# ESP32_S3_Wroom2_Schematic.net
KiCad netlist of a schematic drawn in Altium Designer
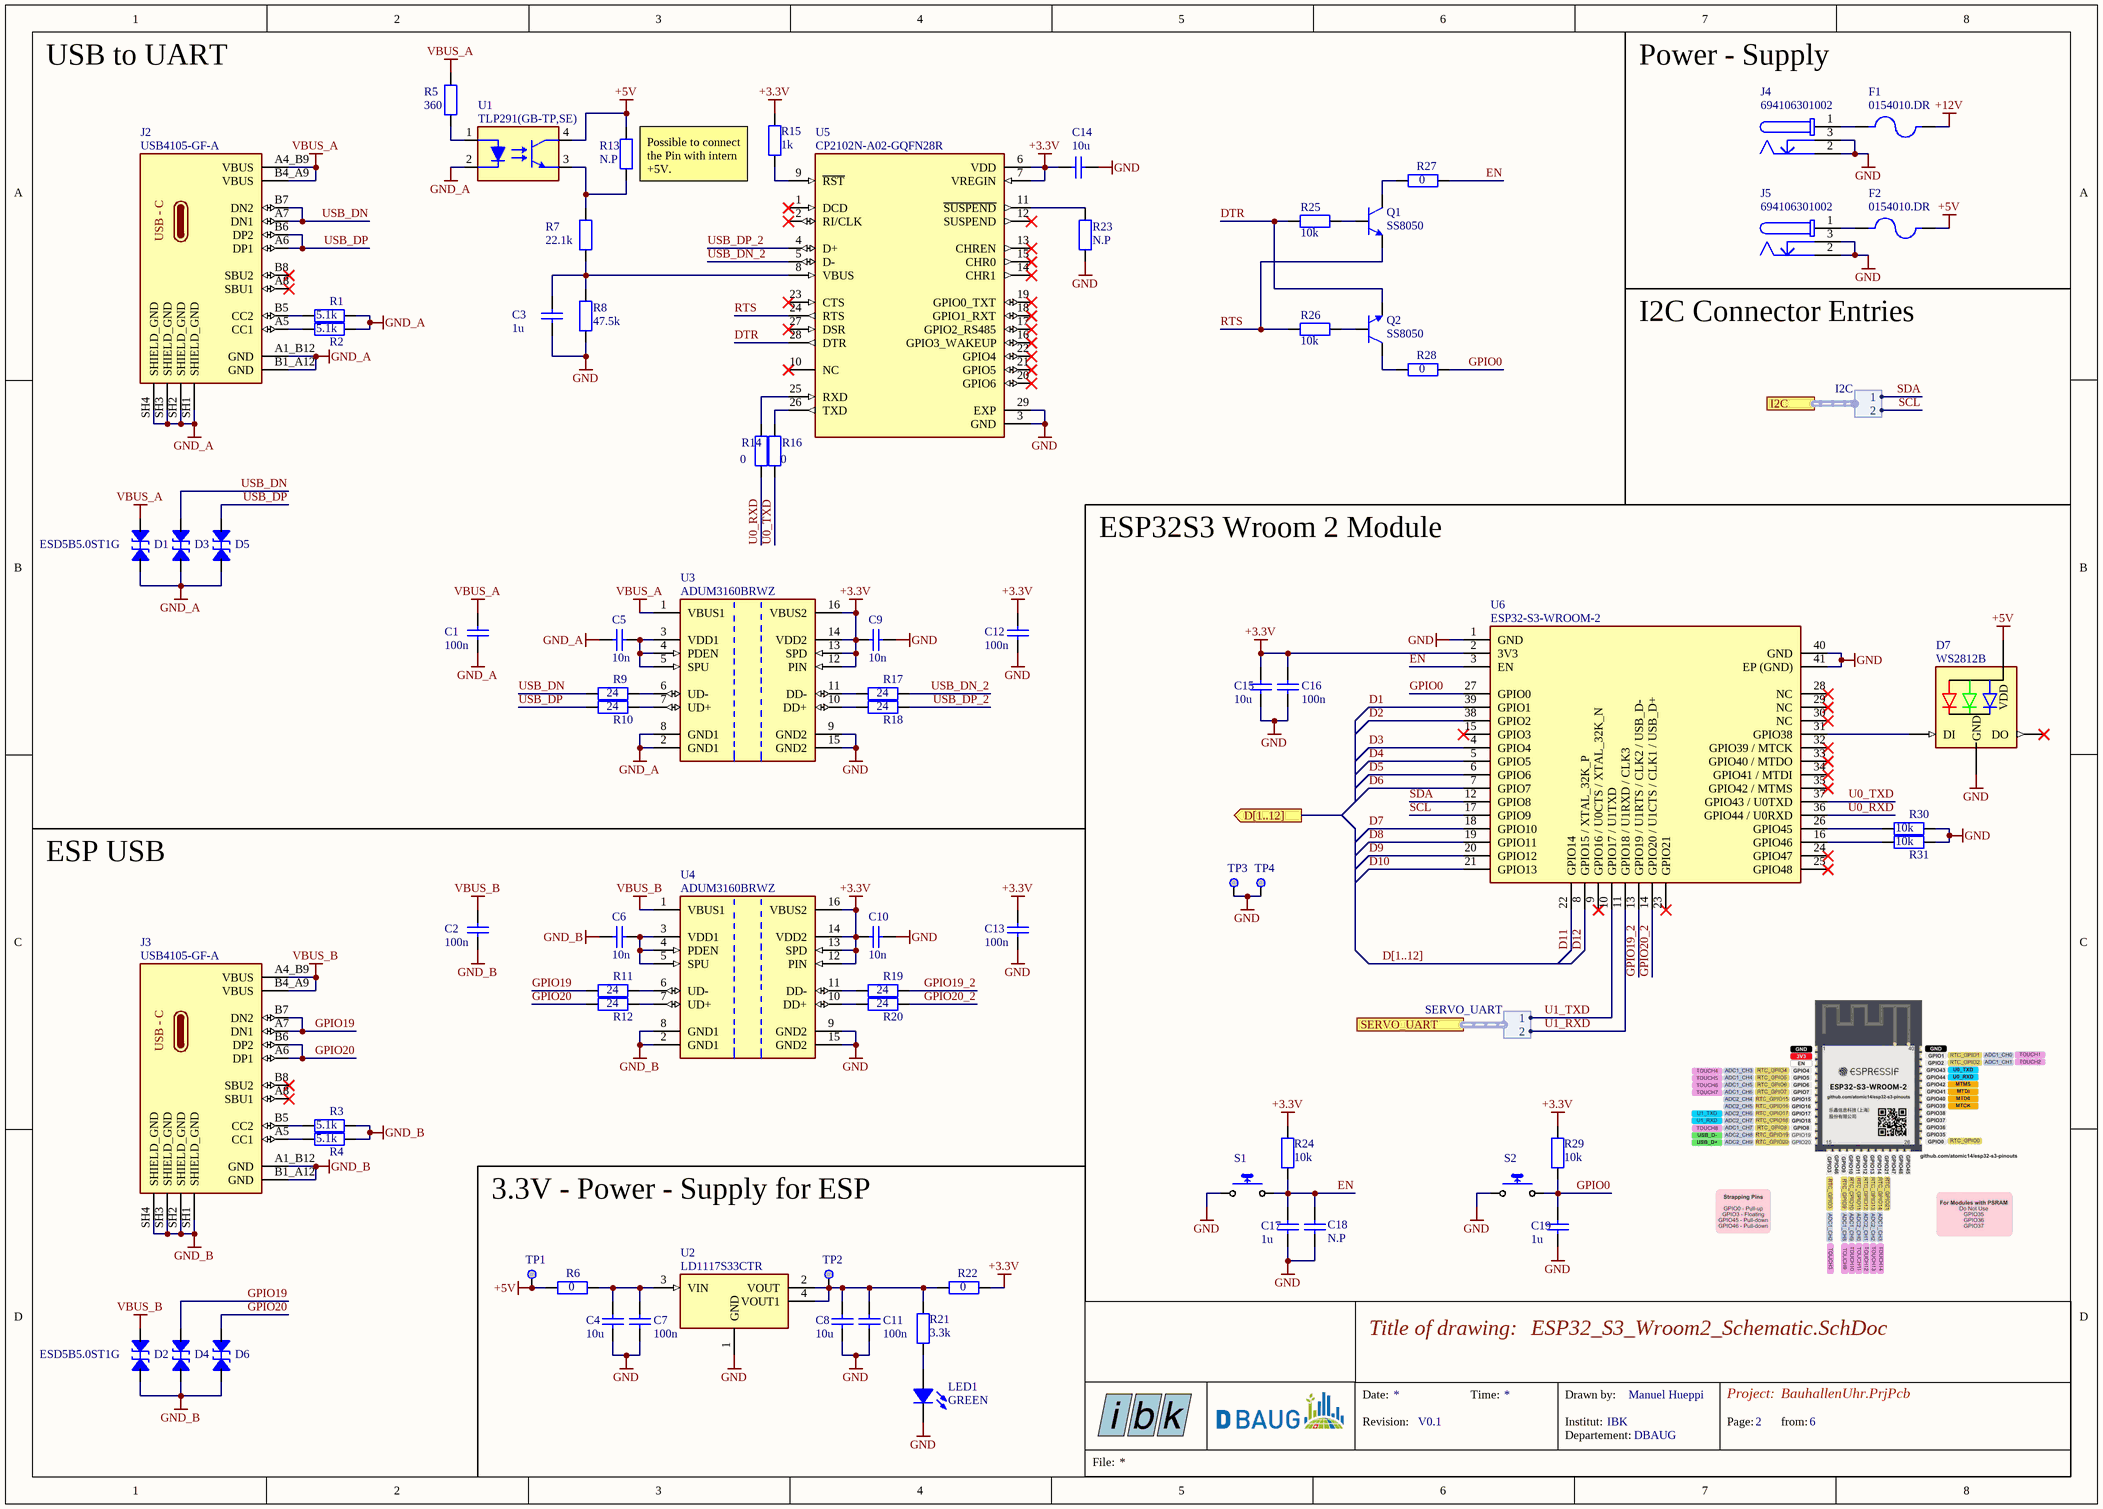
[diagram p0: ESP32_S3_Wroom2_Schematic.SchDoc]

(export (version "E")
  (design (tool "Eeschema 10.0.6"))
  (components
    (comp (ref "C1")
      (value "100n")
      (footprint "PCB_Altium_Library_Manuel:0603_CAPACITOR")
      (description "0603")
      (libsource (lib "Schematic_Altium_Library_Manuel") (part "Capacitor"))
    )
    (comp (ref "C2")
      (value "100n")
      (footprint "PCB_Altium_Library_Manuel:0603_CAPACITOR")
      (description "0603")
      (libsource (lib "Schematic_Altium_Library_Manuel") (part "Capacitor"))
    )
    (comp (ref "C3")
      (value "1u")
      (footprint "PCB_Altium_Library_Manuel:0603_CAPACITOR")
      (description "0603")
      (libsource (lib "Schematic_Altium_Library_Manuel") (part "Capacitor"))
    )
    (comp (ref "C4")
      (value "10u")
      (footprint "PCB_Altium_Library_Manuel:0603_CAPACITOR")
      (description "0603")
      (libsource (lib "Schematic_Altium_Library_Manuel") (part "Capacitor"))
    )
    (comp (ref "C5")
      (value "10n")
      (footprint "PCB_Altium_Library_Manuel:0603_CAPACITOR")
      (description "0603")
      (libsource (lib "Schematic_Altium_Library_Manuel") (part "Capacitor"))
    )
    (comp (ref "C6")
      (value "10n")
      (footprint "PCB_Altium_Library_Manuel:0603_CAPACITOR")
      (description "0603")
      (libsource (lib "Schematic_Altium_Library_Manuel") (part "Capacitor"))
    )
    (comp (ref "C7")
      (value "100n")
      (footprint "PCB_Altium_Library_Manuel:0603_CAPACITOR")
      (description "0603")
      (libsource (lib "Schematic_Altium_Library_Manuel") (part "Capacitor"))
    )
    (comp (ref "C8")
      (value "10u")
      (footprint "PCB_Altium_Library_Manuel:0603_CAPACITOR")
      (description "0603")
      (libsource (lib "Schematic_Altium_Library_Manuel") (part "Capacitor"))
    )
    (comp (ref "C9")
      (value "10n")
      (footprint "PCB_Altium_Library_Manuel:0603_CAPACITOR")
      (description "0603")
      (libsource (lib "Schematic_Altium_Library_Manuel") (part "Capacitor"))
    )
    (comp (ref "C10")
      (value "10n")
      (footprint "PCB_Altium_Library_Manuel:0603_CAPACITOR")
      (description "0603")
      (libsource (lib "Schematic_Altium_Library_Manuel") (part "Capacitor"))
    )
    (comp (ref "C11")
      (value "100n")
      (footprint "PCB_Altium_Library_Manuel:0603_CAPACITOR")
      (description "0603")
      (libsource (lib "Schematic_Altium_Library_Manuel") (part "Capacitor"))
    )
    (comp (ref "C12")
      (value "100n")
      (footprint "PCB_Altium_Library_Manuel:0603_CAPACITOR")
      (description "0603")
      (libsource (lib "Schematic_Altium_Library_Manuel") (part "Capacitor"))
    )
    (comp (ref "C13")
      (value "100n")
      (footprint "PCB_Altium_Library_Manuel:0603_CAPACITOR")
      (description "0603")
      (libsource (lib "Schematic_Altium_Library_Manuel") (part "Capacitor"))
    )
    (comp (ref "C14")
      (value "10u")
      (footprint "PCB_Altium_Library_Manuel:0603_CAPACITOR")
      (description "0603")
      (libsource (lib "Schematic_Altium_Library_Manuel") (part "Capacitor"))
    )
    (comp (ref "C15")
      (value "10u")
      (footprint "PCB_Altium_Library_Manuel:0603_CAPACITOR")
      (description "0603")
      (libsource (lib "Schematic_Altium_Library_Manuel") (part "Capacitor"))
    )
    (comp (ref "C16")
      (value "100n")
      (footprint "PCB_Altium_Library_Manuel:0603_CAPACITOR")
      (description "0603")
      (libsource (lib "Schematic_Altium_Library_Manuel") (part "Capacitor"))
    )
    (comp (ref "C17")
      (value "1u")
      (footprint "PCB_Altium_Library_Manuel:0603_CAPACITOR")
      (description "0603")
      (libsource (lib "Schematic_Altium_Library_Manuel") (part "Capacitor"))
    )
    (comp (ref "C18")
      (value "N.P")
      (footprint "PCB_Altium_Library_Manuel:0603_CAPACITOR")
      (description "0603")
      (libsource (lib "Schematic_Altium_Library_Manuel") (part "Capacitor"))
    )
    (comp (ref "C19")
      (value "1u")
      (footprint "PCB_Altium_Library_Manuel:0603_CAPACITOR")
      (description "0603")
      (libsource (lib "Schematic_Altium_Library_Manuel") (part "Capacitor"))
    )
    (comp (ref "D1")
      (value "ESD5B5.0ST1G")
      (footprint "PCB_Altium_Library_Manuel:ESD_Protecction_Diode")
      (libsource (lib "Schematic_Altium_Library_Manuel") (part "ESD_Protection_Diode"))
    )
    (comp (ref "D2")
      (value "ESD5B5.0ST1G")
      (footprint "PCB_Altium_Library_Manuel:ESD_Protecction_Diode")
      (libsource (lib "Schematic_Altium_Library_Manuel") (part "ESD_Protection_Diode"))
    )
    (comp (ref "D3")
      (value "ESD5B5.0ST1G")
      (footprint "PCB_Altium_Library_Manuel:ESD_Protecction_Diode")
      (libsource (lib "Schematic_Altium_Library_Manuel") (part "ESD_Protection_Diode"))
    )
    (comp (ref "D4")
      (value "ESD5B5.0ST1G")
      (footprint "PCB_Altium_Library_Manuel:ESD_Protecction_Diode")
      (libsource (lib "Schematic_Altium_Library_Manuel") (part "ESD_Protection_Diode"))
    )
    (comp (ref "D5")
      (value "ESD5B5.0ST1G")
      (footprint "PCB_Altium_Library_Manuel:ESD_Protecction_Diode")
      (libsource (lib "Schematic_Altium_Library_Manuel") (part "ESD_Protection_Diode"))
    )
    (comp (ref "D6")
      (value "ESD5B5.0ST1G")
      (footprint "PCB_Altium_Library_Manuel:ESD_Protecction_Diode")
      (libsource (lib "Schematic_Altium_Library_Manuel") (part "ESD_Protection_Diode"))
    )
    (comp (ref "D7")
      (value "WS2812B")
      (footprint "PCB_Altium_Library_Manuel:WS2812B")
      (libsource (lib "Schematic_Altium_Library_Manuel") (part "WS2812B"))
    )
    (comp (ref "F1")
      (value "0154010.DR")
      (footprint "PCB_Altium_Library_Manuel:Fuse")
      (description "FUSE BRD MNT 10A 125VAC/VDC SMD ¦ Littelfuse 0154010.DR.")
      (libsource (lib "Schematic_Altium_Library_Manuel") (part "Fuse"))
    )
    (comp (ref "F2")
      (value "0154010.DR")
      (footprint "PCB_Altium_Library_Manuel:Fuse")
      (description "FUSE BRD MNT 10A 125VAC/VDC SMD ¦ Littelfuse 0154010.DR.")
      (libsource (lib "Schematic_Altium_Library_Manuel") (part "Fuse"))
    )
    (comp (ref "J2")
      (value "USB4105-GF-A")
      (footprint "PCB_Altium_Library_Manuel:USB4105-GF-A")
      (description "USB - C - Port")
      (libsource (lib "Schematic_Altium_Library_Manuel") (part "USB4105-GF-A"))
    )
    (comp (ref "J3")
      (value "USB4105-GF-A")
      (footprint "PCB_Altium_Library_Manuel:USB4105-GF-A")
      (description "USB - C - Port")
      (libsource (lib "Schematic_Altium_Library_Manuel") (part "USB4105-GF-A"))
    )
    (comp (ref "J4")
      (value "694106301002")
      (footprint "PCB_Altium_Library_Manuel:DC_PowerJack_THT")
      (description "DCPowerJack_THT_R/A_Plastic_CenterPin_ Ã˜2.0.")
      (libsource (lib "Schematic_Altium_Library_Manuel") (part "DC_PowerJack_THT"))
    )
    (comp (ref "J5")
      (value "694106301002")
      (footprint "PCB_Altium_Library_Manuel:DC_PowerJack_THT")
      (description "DCPowerJack_THT_R/A_Plastic_CenterPin_ Ã˜2.0.")
      (libsource (lib "Schematic_Altium_Library_Manuel") (part "DC_PowerJack_THT"))
    )
    (comp (ref "LED1")
      (value "GREEN")
      (footprint "PCB_Altium_Library_Manuel:LED_0603, GREEN")
      (description "LED 0603, Green, 3.2 V, 20 mA, 430 mcd")
      (libsource (lib "Schematic_Altium_Library_Manuel") (part "LED_0603, GREEN"))
    )
    (comp (ref "Q1")
      (value "SS8050")
      (footprint "PCB_Altium_Library_Manuel:NPN_Bipolar_Transistor")
      (description "SS8050 SOT - 23.")
      (libsource (lib "Schematic_Altium_Library_Manuel") (part "NPN_Bipolar_Transistor"))
    )
    (comp (ref "Q2")
      (value "SS8050")
      (footprint "PCB_Altium_Library_Manuel:NPN_Bipolar_Transistor")
      (description "SS8050 SOT - 23.")
      (libsource (lib "Schematic_Altium_Library_Manuel") (part "NPN_Bipolar_Transistor"))
    )
    (comp (ref "R1")
      (value "5.1k")
      (footprint "PCB_Altium_Library_Manuel:0603_Resistor")
      (description "0603")
      (libsource (lib "Schematic_Altium_Library_Manuel") (part "Resistor"))
    )
    (comp (ref "R2")
      (value "5.1k")
      (footprint "PCB_Altium_Library_Manuel:0603_Resistor")
      (description "0603")
      (libsource (lib "Schematic_Altium_Library_Manuel") (part "Resistor"))
    )
    (comp (ref "R3")
      (value "5.1k")
      (footprint "PCB_Altium_Library_Manuel:0603_Resistor")
      (description "0603")
      (libsource (lib "Schematic_Altium_Library_Manuel") (part "Resistor"))
    )
    (comp (ref "R4")
      (value "5.1k")
      (footprint "PCB_Altium_Library_Manuel:0603_Resistor")
      (description "0603")
      (libsource (lib "Schematic_Altium_Library_Manuel") (part "Resistor"))
    )
    (comp (ref "R5")
      (value "360")
      (footprint "PCB_Altium_Library_Manuel:0603_Resistor")
      (description "0603")
      (libsource (lib "") (part "Resistor_1"))
    )
    (comp (ref "R6")
      (value "0")
      (footprint "PCB_Altium_Library_Manuel:0603_Resistor")
      (description "0603")
      (libsource (lib "Schematic_Altium_Library_Manuel") (part "Resistor"))
    )
    (comp (ref "R7")
      (value "22.1k")
      (footprint "PCB_Altium_Library_Manuel:0603_Resistor")
      (description "0603")
      (libsource (lib "") (part "Resistor_1"))
    )
    (comp (ref "R8")
      (value "47.5k")
      (footprint "PCB_Altium_Library_Manuel:0603_Resistor")
      (description "0603")
      (libsource (lib "") (part "Resistor_1"))
    )
    (comp (ref "R9")
      (value "24")
      (footprint "PCB_Altium_Library_Manuel:0603_Resistor")
      (description "0603")
      (libsource (lib "Schematic_Altium_Library_Manuel") (part "Resistor"))
    )
    (comp (ref "R10")
      (value "24")
      (footprint "PCB_Altium_Library_Manuel:0603_Resistor")
      (description "0603")
      (libsource (lib "Schematic_Altium_Library_Manuel") (part "Resistor"))
    )
    (comp (ref "R11")
      (value "24")
      (footprint "PCB_Altium_Library_Manuel:0603_Resistor")
      (description "0603")
      (libsource (lib "Schematic_Altium_Library_Manuel") (part "Resistor"))
    )
    (comp (ref "R12")
      (value "24")
      (footprint "PCB_Altium_Library_Manuel:0603_Resistor")
      (description "0603")
      (libsource (lib "Schematic_Altium_Library_Manuel") (part "Resistor"))
    )
    (comp (ref "R13")
      (value "N.P")
      (footprint "PCB_Altium_Library_Manuel:0603_Resistor")
      (description "0603")
      (libsource (lib "") (part "Resistor_1"))
    )
    (comp (ref "R14")
      (value "0")
      (footprint "PCB_Altium_Library_Manuel:0603_Resistor")
      (description "0603")
      (libsource (lib "") (part "Resistor_1"))
    )
    (comp (ref "R15")
      (value "1k")
      (footprint "PCB_Altium_Library_Manuel:0603_Resistor")
      (description "0603")
      (libsource (lib "") (part "Resistor_1"))
    )
    (comp (ref "R16")
      (value "0")
      (footprint "PCB_Altium_Library_Manuel:0603_Resistor")
      (description "0603")
      (libsource (lib "") (part "Resistor_1"))
    )
    (comp (ref "R17")
      (value "24")
      (footprint "PCB_Altium_Library_Manuel:0603_Resistor")
      (description "0603")
      (libsource (lib "Schematic_Altium_Library_Manuel") (part "Resistor"))
    )
    (comp (ref "R18")
      (value "24")
      (footprint "PCB_Altium_Library_Manuel:0603_Resistor")
      (description "0603")
      (libsource (lib "Schematic_Altium_Library_Manuel") (part "Resistor"))
    )
    (comp (ref "R19")
      (value "24")
      (footprint "PCB_Altium_Library_Manuel:0603_Resistor")
      (description "0603")
      (libsource (lib "Schematic_Altium_Library_Manuel") (part "Resistor"))
    )
    (comp (ref "R20")
      (value "24")
      (footprint "PCB_Altium_Library_Manuel:0603_Resistor")
      (description "0603")
      (libsource (lib "Schematic_Altium_Library_Manuel") (part "Resistor"))
    )
    (comp (ref "R21")
      (value "3.3k")
      (footprint "PCB_Altium_Library_Manuel:0603_Resistor")
      (description "0603")
      (libsource (lib "") (part "Resistor_1"))
    )
    (comp (ref "R22")
      (value "0")
      (footprint "PCB_Altium_Library_Manuel:0603_Resistor")
      (description "0603")
      (libsource (lib "Schematic_Altium_Library_Manuel") (part "Resistor"))
    )
    (comp (ref "R23")
      (value "N.P")
      (footprint "PCB_Altium_Library_Manuel:0603_Resistor")
      (description "0603")
      (libsource (lib "") (part "Resistor_1"))
    )
    (comp (ref "R24")
      (value "10k")
      (footprint "PCB_Altium_Library_Manuel:0603_Resistor")
      (description "0603")
      (libsource (lib "") (part "Resistor_1"))
    )
    (comp (ref "R25")
      (value "10k")
      (footprint "PCB_Altium_Library_Manuel:0603_Resistor")
      (description "0603")
      (libsource (lib "") (part "Resistor_2"))
    )
    (comp (ref "R26")
      (value "10k")
      (footprint "PCB_Altium_Library_Manuel:0603_Resistor")
      (description "0603")
      (libsource (lib "") (part "Resistor_2"))
    )
    (comp (ref "R27")
      (value "0")
      (footprint "PCB_Altium_Library_Manuel:0603_Resistor")
      (description "0603")
      (libsource (lib "Schematic_Altium_Library_Manuel") (part "Resistor"))
    )
    (comp (ref "R28")
      (value "0")
      (footprint "PCB_Altium_Library_Manuel:0603_Resistor")
      (description "0603")
      (libsource (lib "Schematic_Altium_Library_Manuel") (part "Resistor"))
    )
    (comp (ref "R29")
      (value "10k")
      (footprint "PCB_Altium_Library_Manuel:0603_Resistor")
      (description "0603")
      (libsource (lib "") (part "Resistor_1"))
    )
    (comp (ref "R30")
      (value "10k")
      (footprint "PCB_Altium_Library_Manuel:0603_Resistor")
      (description "0603")
      (libsource (lib "Schematic_Altium_Library_Manuel") (part "Resistor"))
    )
    (comp (ref "R31")
      (value "10k")
      (footprint "PCB_Altium_Library_Manuel:0603_Resistor")
      (description "0603")
      (libsource (lib "Schematic_Altium_Library_Manuel") (part "Resistor"))
    )
    (comp (ref "S1")
      (value "?")
      (footprint "PCB_Altium_Library_Manuel:PTS636SK25SMTR")
      (libsource (lib "Schematic_Altium_Library_Manuel") (part "Button"))
    )
    (comp (ref "S2")
      (value "?")
      (footprint "PCB_Altium_Library_Manuel:PTS636SK25SMTR")
      (libsource (lib "Schematic_Altium_Library_Manuel") (part "Button"))
    )
    (comp (ref "TP1")
      (value "Testpoint S2761-46R")
      (footprint "PCB_Altium_Library_Manuel:Testpoint S2761-46R")
      (description "Prüfstecker und Messbuchsen EZ BoardWare S27 SMT Mini Test Terminal, Reel")
      (libsource (lib "Schematic_Altium_Library_Manuel") (part "Testpoint S2761-46R"))
    )
    (comp (ref "TP2")
      (value "Testpoint S2761-46R")
      (footprint "PCB_Altium_Library_Manuel:Testpoint S2761-46R")
      (description "Prüfstecker und Messbuchsen EZ BoardWare S27 SMT Mini Test Terminal, Reel")
      (libsource (lib "Schematic_Altium_Library_Manuel") (part "Testpoint S2761-46R"))
    )
    (comp (ref "TP3")
      (value "Testpoint S2761-46R")
      (footprint "PCB_Altium_Library_Manuel:Testpoint S2761-46R")
      (description "Prüfstecker und Messbuchsen EZ BoardWare S27 SMT Mini Test Terminal, Reel")
      (libsource (lib "Schematic_Altium_Library_Manuel") (part "Testpoint S2761-46R"))
    )
    (comp (ref "TP4")
      (value "Testpoint S2761-46R")
      (footprint "PCB_Altium_Library_Manuel:Testpoint S2761-46R")
      (description "Prüfstecker und Messbuchsen EZ BoardWare S27 SMT Mini Test Terminal, Reel")
      (libsource (lib "Schematic_Altium_Library_Manuel") (part "Testpoint S2761-46R"))
    )
    (comp (ref "U1")
      (value "TLP291(GB-TP,SE)")
      (footprint "PCB_Altium_Library_Manuel:Optocoupler")
      (description "Optoisolator Transistor Output 3750Vrms 1 Channel 4-SO.")
      (libsource (lib "Schematic_Altium_Library_Manuel") (part "Optocoupler"))
    )
    (comp (ref "U2")
      (value "LD1117S33CTR")
      (footprint "PCB_Altium_Library_Manuel:LD1117S33CTR")
      (description "LDO, 3.3V and 800mA.")
      (libsource (lib "Schematic_Altium_Library_Manuel") (part "LD1117S33CTR"))
    )
    (comp (ref "U3")
      (value "ADUM3160BRWZ")
      (footprint "PCB_Altium_Library_Manuel:USB_Digital_Isolator_A")
      (description "DGT ISOL 2500VRMS 2CH USB 16SOIC.")
      (libsource (lib "Schematic_Altium_Library_Manuel") (part "USB_Digital_Isolator"))
    )
    (comp (ref "U4")
      (value "ADUM3160BRWZ")
      (footprint "PCB_Altium_Library_Manuel:USB_Digital_Isolator_A")
      (description "DGT ISOL 2500VRMS 2CH USB 16SOIC.")
      (libsource (lib "Schematic_Altium_Library_Manuel") (part "USB_Digital_Isolator"))
    )
    (comp (ref "U5")
      (value "CP2102N-A02-GQFN28R")
      (footprint "PCB_Altium_Library_Manuel:CP2102N-A02-GQFN28R")
      (description "USB to UART bridge.")
      (libsource (lib "Schematic_Altium_Library_Manuel") (part "CP2102N-A02-GQFN28R"))
    )
    (comp (ref "U6")
      (value "ESP32-S3-WROOM-2")
      (footprint "PCB_Altium_Library_Manuel:ESP32-S3-WROOM-2")
      (description "Bluetooth, WiFi 802.11b/g/n, Bluetooth v5.0 Transceiver Module 2.4GHz PCB Trace Surface Mount")
      (fields
        (field (name "MANUFACTURER") "Espressif Systems")
        (field (name "MANUFACTURER PART NUMBER") "ESP32-S3-WROOM-2-N32R16V")
        (field (name "LATEST REVISION MADE BY") "Simon Gimple")
      )
      (libsource (lib "Schematic_Altium_Library_Manuel") (part "ESP32-S3-WROOM-2-N32R16V"))
    )
  )
  (nets
    (net (code "3") (name "+3.3V") (class "Default")
      (node (ref "C10") (pin "1") (pinfunction "1_1") (pintype "passive"))
      (node (ref "C12") (pin "2") (pinfunction "2_2") (pintype "passive"))
      (node (ref "C13") (pin "2") (pinfunction "2_2") (pintype "passive"))
      (node (ref "C14") (pin "2") (pinfunction "2_2") (pintype "passive"))
      (node (ref "C15") (pin "2") (pinfunction "2_2") (pintype "passive"))
      (node (ref "C16") (pin "2") (pinfunction "2_2") (pintype "passive"))
      (node (ref "C9") (pin "1") (pinfunction "1_1") (pintype "passive"))
      (node (ref "R15") (pin "2") (pinfunction "2_2") (pintype "passive"))
      (node (ref "R22") (pin "2") (pinfunction "2_2") (pintype "passive"))
      (node (ref "R24") (pin "2") (pinfunction "2_2") (pintype "passive"))
      (node (ref "R29") (pin "2") (pinfunction "2_2") (pintype "passive"))
      (node (ref "U3") (pin "12") (pinfunction "PIN_12") (pintype "input"))
      (node (ref "U3") (pin "13") (pinfunction "SPD_13") (pintype "input"))
      (node (ref "U3") (pin "14") (pinfunction "VDD2_14") (pintype "power_in"))
      (node (ref "U3") (pin "16") (pinfunction "VBUS2_16") (pintype "power_in"))
      (node (ref "U4") (pin "12") (pinfunction "PIN_12") (pintype "input"))
      (node (ref "U4") (pin "13") (pinfunction "SPD_13") (pintype "input"))
      (node (ref "U4") (pin "14") (pinfunction "VDD2_14") (pintype "power_in"))
      (node (ref "U4") (pin "16") (pinfunction "VBUS2_16") (pintype "power_in"))
      (node (ref "U5") (pin "6") (pinfunction "VDD_6") (pintype "power_in"))
      (node (ref "U5") (pin "7") (pinfunction "VREGIN_7") (pintype "input"))
      (node (ref "U6") (pin "2") (pinfunction "3V3_2") (pintype "passive"))
    )
    (net (code "4") (name "+5V") (class "Default")
      (node (ref "D7") (pin "1-VDD") (pinfunction "VDD_1-VDD") (pintype "power_in"))
      (node (ref "F2") (pin "2") (pinfunction "2_2") (pintype "passive"))
      (node (ref "R13") (pin "2") (pinfunction "2_2") (pintype "passive"))
      (node (ref "R6") (pin "1") (pinfunction "1_1") (pintype "passive"))
      (node (ref "TP1") (pin "1") (pinfunction "1_1") (pintype "passive"))
      (node (ref "U1") (pin "4") (pinfunction "COL_4") (pintype "passive"))
    )
    (net (code "5") (name "+12V") (class "Default")
      (node (ref "F1") (pin "2") (pinfunction "2_2") (pintype "passive"))
    )
    (net (code "6") (name "/D1") (class "Default")
      (node (ref "U6") (pin "39") (pinfunction "GPIO1_39") (pintype "passive"))
    )
    (net (code "7") (name "/D2") (class "Default")
      (node (ref "U6") (pin "38") (pinfunction "GPIO2_38") (pintype "passive"))
    )
    (net (code "8") (name "/D3") (class "Default")
      (node (ref "U6") (pin "4") (pinfunction "GPIO4_4") (pintype "passive"))
    )
    (net (code "9") (name "/D4") (class "Default")
      (node (ref "U6") (pin "5") (pinfunction "GPIO5_5") (pintype "passive"))
    )
    (net (code "10") (name "/D5") (class "Default")
      (node (ref "U6") (pin "6") (pinfunction "GPIO6_6") (pintype "passive"))
    )
    (net (code "11") (name "/D6") (class "Default")
      (node (ref "U6") (pin "7") (pinfunction "GPIO7_7") (pintype "passive"))
    )
    (net (code "12") (name "/D7") (class "Default")
      (node (ref "U6") (pin "18") (pinfunction "GPIO10_18") (pintype "passive"))
    )
    (net (code "13") (name "/D8") (class "Default")
      (node (ref "U6") (pin "19") (pinfunction "GPIO11_19") (pintype "passive"))
    )
    (net (code "14") (name "/D9") (class "Default")
      (node (ref "U6") (pin "20") (pinfunction "GPIO12_20") (pintype "passive"))
    )
    (net (code "15") (name "/D10") (class "Default")
      (node (ref "U6") (pin "21") (pinfunction "GPIO13_21") (pintype "passive"))
    )
    (net (code "16") (name "/D11") (class "Default")
      (node (ref "U6") (pin "22") (pinfunction "GPIO14_22") (pintype "passive"))
    )
    (net (code "17") (name "/D12") (class "Default")
      (node (ref "U6") (pin "8") (pinfunction "GPIO15_/_XTAL_32K_P_8") (pintype "passive"))
    )
    (net (code "18") (name "/DTR") (class "Default")
      (node (ref "Q2") (pin "2") (pinfunction "E_2") (pintype "passive"))
      (node (ref "R25") (pin "2") (pinfunction "2_2") (pintype "passive"))
      (node (ref "U5") (pin "28") (pinfunction "DTR_28") (pintype "output"))
    )
    (net (code "20") (name "/EN") (class "Default")
      (node (ref "C17") (pin "2") (pinfunction "2_2") (pintype "passive"))
      (node (ref "C18") (pin "2") (pinfunction "2_2") (pintype "passive"))
      (node (ref "R24") (pin "1") (pinfunction "1_1") (pintype "passive"))
      (node (ref "R27") (pin "2") (pinfunction "2_2") (pintype "passive"))
      (node (ref "S1") (pin "2") (pinfunction "2_2") (pintype "passive"))
      (node (ref "U6") (pin "3") (pinfunction "EN_3") (pintype "passive"))
    )
    (net (code "21") (name "/GPIO0") (class "Default")
      (node (ref "C19") (pin "2") (pinfunction "2_2") (pintype "passive"))
      (node (ref "R28") (pin "2") (pinfunction "2_2") (pintype "passive"))
      (node (ref "R29") (pin "1") (pinfunction "1_1") (pintype "passive"))
      (node (ref "S2") (pin "2") (pinfunction "2_2") (pintype "passive"))
      (node (ref "U6") (pin "27") (pinfunction "GPIO0_27") (pintype "passive"))
    )
    (net (code "22") (name "/GPIO19") (class "Default")
      (node (ref "D4") (pin "K") (pinfunction "P$2_K") (pintype "passive"))
      (node (ref "J3") (pin "A7") (pinfunction "DN1_A7") (pintype "bidirectional"))
      (node (ref "J3") (pin "B7") (pinfunction "DN2_B7") (pintype "bidirectional"))
      (node (ref "R11") (pin "1") (pinfunction "1_1") (pintype "passive"))
    )
    (net (code "23") (name "/GPIO19_2") (class "Default")
      (node (ref "R19") (pin "2") (pinfunction "2_2") (pintype "passive"))
      (node (ref "U6") (pin "13") (pinfunction "GPIO19_/_U1RTS_/_CLK2_/_USB_D-_13") (pintype "passive"))
    )
    (net (code "24") (name "/GPIO20") (class "Default")
      (node (ref "D6") (pin "K") (pinfunction "P$2_K") (pintype "passive"))
      (node (ref "J3") (pin "A6") (pinfunction "DP1_A6") (pintype "bidirectional"))
      (node (ref "J3") (pin "B6") (pinfunction "DP2_B6") (pintype "bidirectional"))
      (node (ref "R12") (pin "1") (pinfunction "1_1") (pintype "passive"))
    )
    (net (code "25") (name "/GPIO20_2") (class "Default")
      (node (ref "R20") (pin "2") (pinfunction "2_2") (pintype "passive"))
      (node (ref "U6") (pin "14") (pinfunction "GPIO20_/_U1CTS_/_CLK1_/_USB_D+_14") (pintype "passive"))
    )
    (net (code "26") (name "/RTS") (class "Default")
      (node (ref "Q1") (pin "2") (pinfunction "E_2") (pintype "passive"))
      (node (ref "R26") (pin "2") (pinfunction "2_2") (pintype "passive"))
      (node (ref "U5") (pin "24") (pinfunction "RTS_24") (pintype "output"))
    )
    (net (code "27") (name "/SCL") (class "Default")
      (node (ref "U6") (pin "17") (pinfunction "GPIO9_17") (pintype "passive"))
    )
    (net (code "28") (name "/SDA") (class "Default")
      (node (ref "U6") (pin "12") (pinfunction "GPIO8_12") (pintype "passive"))
    )
    (net (code "29") (name "/U0_RXD") (class "Default")
      (node (ref "R14") (pin "1") (pinfunction "1_1") (pintype "passive"))
      (node (ref "U6") (pin "36") (pinfunction "GPIO44_/_U0RXD_36") (pintype "passive"))
    )
    (net (code "30") (name "/U0_TXD") (class "Default")
      (node (ref "R16") (pin "1") (pinfunction "1_1") (pintype "passive"))
      (node (ref "U6") (pin "37") (pinfunction "GPIO43_/_U0TXD_37") (pintype "passive"))
    )
    (net (code "31") (name "/U1_RXD") (class "Default")
      (node (ref "U6") (pin "11") (pinfunction "GPIO18_/_U1RXD_/_CLK3_11") (pintype "passive"))
    )
    (net (code "32") (name "/U1_TXD") (class "Default")
      (node (ref "U6") (pin "10") (pinfunction "GPIO17_/_U1TXD_10") (pintype "passive"))
    )
    (net (code "33") (name "/USB_DN") (class "Default")
      (node (ref "D3") (pin "K") (pinfunction "P$2_K") (pintype "passive"))
      (node (ref "J2") (pin "A7") (pinfunction "DN1_A7") (pintype "bidirectional"))
      (node (ref "J2") (pin "B7") (pinfunction "DN2_B7") (pintype "bidirectional"))
      (node (ref "R9") (pin "1") (pinfunction "1_1") (pintype "passive"))
    )
    (net (code "34") (name "/USB_DN_2") (class "Default")
      (node (ref "R17") (pin "2") (pinfunction "2_2") (pintype "passive"))
      (node (ref "U5") (pin "5") (pinfunction "D-_5") (pintype "bidirectional"))
    )
    (net (code "35") (name "/USB_DP") (class "Default")
      (node (ref "D5") (pin "K") (pinfunction "P$2_K") (pintype "passive"))
      (node (ref "J2") (pin "A6") (pinfunction "DP1_A6") (pintype "bidirectional"))
      (node (ref "J2") (pin "B6") (pinfunction "DP2_B6") (pintype "bidirectional"))
      (node (ref "R10") (pin "1") (pinfunction "1_1") (pintype "passive"))
    )
    (net (code "36") (name "/USB_DP_2") (class "Default")
      (node (ref "R18") (pin "2") (pinfunction "2_2") (pintype "passive"))
      (node (ref "U5") (pin "4") (pinfunction "D+_4") (pintype "bidirectional"))
    )
    (net (code "39") (name "GND") (class "Default")
      (node (ref "C10") (pin "2") (pinfunction "2_2") (pintype "passive"))
      (node (ref "C11") (pin "1") (pinfunction "1_1") (pintype "passive"))
      (node (ref "C12") (pin "1") (pinfunction "1_1") (pintype "passive"))
      (node (ref "C13") (pin "1") (pinfunction "1_1") (pintype "passive"))
      (node (ref "C14") (pin "1") (pinfunction "1_1") (pintype "passive"))
      (node (ref "C15") (pin "1") (pinfunction "1_1") (pintype "passive"))
      (node (ref "C16") (pin "1") (pinfunction "1_1") (pintype "passive"))
      (node (ref "C17") (pin "1") (pinfunction "1_1") (pintype "passive"))
      (node (ref "C18") (pin "1") (pinfunction "1_1") (pintype "passive"))
      (node (ref "C19") (pin "1") (pinfunction "1_1") (pintype "passive"))
      (node (ref "C3") (pin "2") (pinfunction "2_2") (pintype "passive"))
      (node (ref "C4") (pin "1") (pinfunction "1_1") (pintype "passive"))
      (node (ref "C7") (pin "1") (pinfunction "1_1") (pintype "passive"))
      (node (ref "C8") (pin "1") (pinfunction "1_1") (pintype "passive"))
      (node (ref "C9") (pin "2") (pinfunction "2_2") (pintype "passive"))
      (node (ref "D7") (pin "3-GND") (pinfunction "GND_3-GND") (pintype "power_in"))
      (node (ref "J4") (pin "2") (pinfunction "2_2") (pintype "passive"))
      (node (ref "J4") (pin "3") (pinfunction "3_3") (pintype "passive"))
      (node (ref "J5") (pin "2") (pinfunction "2_2") (pintype "passive"))
      (node (ref "J5") (pin "3") (pinfunction "3_3") (pintype "passive"))
      (node (ref "LED1") (pin "K") (pinfunction "K_K") (pintype "passive"))
      (node (ref "R23") (pin "1") (pinfunction "1_1") (pintype "passive"))
      (node (ref "R30") (pin "2") (pinfunction "2_2") (pintype "passive"))
      (node (ref "R31") (pin "2") (pinfunction "2_2") (pintype "passive"))
      (node (ref "R8") (pin "1") (pinfunction "1_1") (pintype "passive"))
      (node (ref "S1") (pin "1") (pinfunction "1_1") (pintype "passive"))
      (node (ref "S2") (pin "1") (pinfunction "1_1") (pintype "passive"))
      (node (ref "TP3") (pin "1") (pinfunction "1_1") (pintype "passive"))
      (node (ref "TP4") (pin "1") (pinfunction "1_1") (pintype "passive"))
      (node (ref "U2") (pin "1") (pinfunction "GND_1") (pintype "power_in"))
      (node (ref "U3") (pin "15") (pinfunction "GND2_15") (pintype "power_in"))
      (node (ref "U3") (pin "9") (pinfunction "GND2_9") (pintype "power_in"))
      (node (ref "U4") (pin "15") (pinfunction "GND2_15") (pintype "power_in"))
      (node (ref "U4") (pin "9") (pinfunction "GND2_9") (pintype "power_in"))
      (node (ref "U5") (pin "29") (pinfunction "EXP_29") (pintype "power_in"))
      (node (ref "U5") (pin "3") (pinfunction "GND_3") (pintype "power_in"))
      (node (ref "U6") (pin "1") (pinfunction "GND_1") (pintype "passive"))
      (node (ref "U6") (pin "40") (pinfunction "GND_40") (pintype "passive"))
      (node (ref "U6") (pin "41") (pinfunction "EP_(GND)_41") (pintype "passive"))
    )
    (net (code "40") (name "GND_A") (class "Default")
      (node (ref "C1") (pin "1") (pinfunction "1_1") (pintype "passive"))
      (node (ref "C5") (pin "2") (pinfunction "2_2") (pintype "passive"))
      (node (ref "D1") (pin "A") (pinfunction "P$1_A") (pintype "passive"))
      (node (ref "D3") (pin "A") (pinfunction "P$1_A") (pintype "passive"))
      (node (ref "D5") (pin "A") (pinfunction "P$1_A") (pintype "passive"))
      (node (ref "J2") (pin "A1_B12") (pinfunction "GND_A1_B12") (pintype "power_in"))
      (node (ref "J2") (pin "B1_A12") (pinfunction "GND_B1_A12") (pintype "power_in"))
      (node (ref "J2") (pin "SH1") (pinfunction "SHIELD_GND_SH1") (pintype "power_in"))
      (node (ref "J2") (pin "SH2") (pinfunction "SHIELD_GND_SH2") (pintype "power_in"))
      (node (ref "J2") (pin "SH3") (pinfunction "SHIELD_GND_SH3") (pintype "power_in"))
      (node (ref "J2") (pin "SH4") (pinfunction "SHIELD_GND_SH4") (pintype "power_in"))
      (node (ref "R1") (pin "2") (pinfunction "2_2") (pintype "passive"))
      (node (ref "R2") (pin "2") (pinfunction "2_2") (pintype "passive"))
      (node (ref "U1") (pin "2") (pinfunction "C_2") (pintype "passive"))
      (node (ref "U3") (pin "2") (pinfunction "GND1_2") (pintype "power_in"))
      (node (ref "U3") (pin "8") (pinfunction "GND1_8") (pintype "power_in"))
    )
    (net (code "41") (name "GND_B") (class "Default")
      (node (ref "C2") (pin "1") (pinfunction "1_1") (pintype "passive"))
      (node (ref "C6") (pin "2") (pinfunction "2_2") (pintype "passive"))
      (node (ref "D2") (pin "A") (pinfunction "P$1_A") (pintype "passive"))
      (node (ref "D4") (pin "A") (pinfunction "P$1_A") (pintype "passive"))
      (node (ref "D6") (pin "A") (pinfunction "P$1_A") (pintype "passive"))
      (node (ref "J3") (pin "A1_B12") (pinfunction "GND_A1_B12") (pintype "power_in"))
      (node (ref "J3") (pin "B1_A12") (pinfunction "GND_B1_A12") (pintype "power_in"))
      (node (ref "J3") (pin "SH1") (pinfunction "SHIELD_GND_SH1") (pintype "power_in"))
      (node (ref "J3") (pin "SH2") (pinfunction "SHIELD_GND_SH2") (pintype "power_in"))
      (node (ref "J3") (pin "SH3") (pinfunction "SHIELD_GND_SH3") (pintype "power_in"))
      (node (ref "J3") (pin "SH4") (pinfunction "SHIELD_GND_SH4") (pintype "power_in"))
      (node (ref "R3") (pin "2") (pinfunction "2_2") (pintype "passive"))
      (node (ref "R4") (pin "2") (pinfunction "2_2") (pintype "passive"))
      (node (ref "U4") (pin "2") (pinfunction "GND1_2") (pintype "power_in"))
      (node (ref "U4") (pin "8") (pinfunction "GND1_8") (pintype "power_in"))
    )
    (net (code "42") (name "Net-(D7-DI)") (class "Default")
      (node (ref "D7") (pin "4-DIN") (pinfunction "DI_4-DIN") (pintype "input"))
      (node (ref "U6") (pin "31") (pinfunction "GPIO38_31") (pintype "passive"))
    )
    (net (code "43") (name "Net-(F1-Pad1)") (class "Default")
      (node (ref "F1") (pin "1") (pinfunction "1_1") (pintype "passive"))
      (node (ref "J4") (pin "1") (pinfunction "1_1") (pintype "passive"))
    )
    (net (code "44") (name "Net-(F2-Pad1)") (class "Default")
      (node (ref "F2") (pin "1") (pinfunction "1_1") (pintype "passive"))
      (node (ref "J5") (pin "1") (pinfunction "1_1") (pintype "passive"))
    )
    (net (code "45") (name "Net-(J2-CC1)") (class "Default")
      (node (ref "J2") (pin "A5") (pinfunction "CC1_A5") (pintype "bidirectional"))
      (node (ref "R2") (pin "1") (pinfunction "1_1") (pintype "passive"))
    )
    (net (code "46") (name "Net-(J2-CC2)") (class "Default")
      (node (ref "J2") (pin "B5") (pinfunction "CC2_B5") (pintype "bidirectional"))
      (node (ref "R1") (pin "1") (pinfunction "1_1") (pintype "passive"))
    )
    (net (code "47") (name "Net-(J3-CC1)") (class "Default")
      (node (ref "J3") (pin "A5") (pinfunction "CC1_A5") (pintype "bidirectional"))
      (node (ref "R4") (pin "1") (pinfunction "1_1") (pintype "passive"))
    )
    (net (code "48") (name "Net-(J3-CC2)") (class "Default")
      (node (ref "J3") (pin "B5") (pinfunction "CC2_B5") (pintype "bidirectional"))
      (node (ref "R3") (pin "1") (pinfunction "1_1") (pintype "passive"))
    )
    (net (code "49") (name "Net-(LED1-PadA)") (class "Default")
      (node (ref "LED1") (pin "A") (pinfunction "A_A") (pintype "passive"))
      (node (ref "R21") (pin "1") (pinfunction "1_1") (pintype "passive"))
    )
    (net (code "50") (name "Net-(Q1-B)") (class "Default")
      (node (ref "Q1") (pin "1") (pinfunction "B_1") (pintype "passive"))
      (node (ref "R25") (pin "1") (pinfunction "1_1") (pintype "passive"))
    )
    (net (code "51") (name "Net-(Q1-C)") (class "Default")
      (node (ref "Q1") (pin "3") (pinfunction "C_3") (pintype "passive"))
      (node (ref "R27") (pin "1") (pinfunction "1_1") (pintype "passive"))
    )
    (net (code "52") (name "Net-(Q2-B)") (class "Default")
      (node (ref "Q2") (pin "1") (pinfunction "B_1") (pintype "passive"))
      (node (ref "R26") (pin "1") (pinfunction "1_1") (pintype "passive"))
    )
    (net (code "53") (name "Net-(Q2-C)") (class "Default")
      (node (ref "Q2") (pin "3") (pinfunction "C_3") (pintype "passive"))
      (node (ref "R28") (pin "1") (pinfunction "1_1") (pintype "passive"))
    )
    (net (code "54") (name "Net-(U1-A)") (class "Default")
      (node (ref "R5") (pin "1") (pinfunction "1_1") (pintype "passive"))
      (node (ref "U1") (pin "1") (pinfunction "A_1") (pintype "passive"))
    )
    (net (code "55") (name "Net-(U1-EMIT)") (class "Default")
      (node (ref "R13") (pin "1") (pinfunction "1_1") (pintype "passive"))
      (node (ref "R7") (pin "2") (pinfunction "2_2") (pintype "passive"))
      (node (ref "U1") (pin "3") (pinfunction "EMIT_3") (pintype "passive"))
    )
    (net (code "56") (name "Net-(U2-VIN)") (class "Default")
      (node (ref "C4") (pin "2") (pinfunction "2_2") (pintype "passive"))
      (node (ref "C7") (pin "2") (pinfunction "2_2") (pintype "passive"))
      (node (ref "R6") (pin "2") (pinfunction "2_2") (pintype "passive"))
      (node (ref "U2") (pin "3") (pinfunction "VIN_3") (pintype "input"))
    )
    (net (code "57") (name "Net-(U2-VOUT)") (class "Default")
      (node (ref "C11") (pin "2") (pinfunction "2_2") (pintype "passive"))
      (node (ref "C8") (pin "2") (pinfunction "2_2") (pintype "passive"))
      (node (ref "R21") (pin "2") (pinfunction "2_2") (pintype "passive"))
      (node (ref "R22") (pin "1") (pinfunction "1_1") (pintype "passive"))
      (node (ref "TP2") (pin "1") (pinfunction "1_1") (pintype "passive"))
      (node (ref "U2") (pin "2") (pinfunction "VOUT_2") (pintype "power_in"))
      (node (ref "U2") (pin "4") (pinfunction "VOUT1_4") (pintype "power_in"))
    )
    (net (code "58") (name "Net-(U3-DD+)") (class "Default")
      (node (ref "R18") (pin "1") (pinfunction "1_1") (pintype "passive"))
      (node (ref "U3") (pin "10") (pinfunction "DD+_10") (pintype "bidirectional"))
    )
    (net (code "59") (name "Net-(U3-DD-)") (class "Default")
      (node (ref "R17") (pin "1") (pinfunction "1_1") (pintype "passive"))
      (node (ref "U3") (pin "11") (pinfunction "DD-_11") (pintype "bidirectional"))
    )
    (net (code "60") (name "Net-(U3-PDEN)") (class "Default")
      (node (ref "C5") (pin "1") (pinfunction "1_1") (pintype "passive"))
      (node (ref "U3") (pin "3") (pinfunction "VDD1_3") (pintype "power_in"))
      (node (ref "U3") (pin "4") (pinfunction "PDEN_4") (pintype "input"))
      (node (ref "U3") (pin "5") (pinfunction "SPU_5") (pintype "input"))
    )
    (net (code "61") (name "Net-(U3-UD+)") (class "Default")
      (node (ref "R10") (pin "2") (pinfunction "2_2") (pintype "passive"))
      (node (ref "U3") (pin "7") (pinfunction "UD+_7") (pintype "bidirectional"))
    )
    (net (code "62") (name "Net-(U3-UD-)") (class "Default")
      (node (ref "R9") (pin "2") (pinfunction "2_2") (pintype "passive"))
      (node (ref "U3") (pin "6") (pinfunction "UD-_6") (pintype "bidirectional"))
    )
    (net (code "63") (name "Net-(U4-DD+)") (class "Default")
      (node (ref "R20") (pin "1") (pinfunction "1_1") (pintype "passive"))
      (node (ref "U4") (pin "10") (pinfunction "DD+_10") (pintype "bidirectional"))
    )
    (net (code "64") (name "Net-(U4-DD-)") (class "Default")
      (node (ref "R19") (pin "1") (pinfunction "1_1") (pintype "passive"))
      (node (ref "U4") (pin "11") (pinfunction "DD-_11") (pintype "bidirectional"))
    )
    (net (code "65") (name "Net-(U4-PDEN)") (class "Default")
      (node (ref "C6") (pin "1") (pinfunction "1_1") (pintype "passive"))
      (node (ref "U4") (pin "3") (pinfunction "VDD1_3") (pintype "power_in"))
      (node (ref "U4") (pin "4") (pinfunction "PDEN_4") (pintype "input"))
      (node (ref "U4") (pin "5") (pinfunction "SPU_5") (pintype "input"))
    )
    (net (code "66") (name "Net-(U4-UD+)") (class "Default")
      (node (ref "R12") (pin "2") (pinfunction "2_2") (pintype "passive"))
      (node (ref "U4") (pin "7") (pinfunction "UD+_7") (pintype "bidirectional"))
    )
    (net (code "67") (name "Net-(U4-UD-)") (class "Default")
      (node (ref "R11") (pin "2") (pinfunction "2_2") (pintype "passive"))
      (node (ref "U4") (pin "6") (pinfunction "UD-_6") (pintype "bidirectional"))
    )
    (net (code "68") (name "Net-(U5-RXD)") (class "Default")
      (node (ref "R14") (pin "2") (pinfunction "2_2") (pintype "passive"))
      (node (ref "U5") (pin "25") (pinfunction "RXD_25") (pintype "input"))
    )
    (net (code "69") (name "Net-(U5-TXD)") (class "Default")
      (node (ref "R16") (pin "2") (pinfunction "2_2") (pintype "passive"))
      (node (ref "U5") (pin "26") (pinfunction "TXD_26") (pintype "output"))
    )
    (net (code "70") (name "Net-(U5-VBUS)") (class "Default")
      (node (ref "C3") (pin "1") (pinfunction "1_1") (pintype "passive"))
      (node (ref "R7") (pin "1") (pinfunction "1_1") (pintype "passive"))
      (node (ref "R8") (pin "2") (pinfunction "2_2") (pintype "passive"))
      (node (ref "U5") (pin "8") (pinfunction "VBUS_8") (pintype "input"))
    )
    (net (code "71") (name "Net-(U5-~{RST})") (class "Default")
      (node (ref "R15") (pin "1") (pinfunction "1_1") (pintype "passive"))
      (node (ref "U5") (pin "9") (pinfunction "~{RST}_9") (pintype "input"))
    )
    (net (code "72") (name "Net-(U5-~{SUSPEND})") (class "Default")
      (node (ref "R23") (pin "2") (pinfunction "2_2") (pintype "passive"))
      (node (ref "U5") (pin "11") (pinfunction "~{SUSPEND}_11") (pintype "output"))
    )
    (net (code "73") (name "Net-(U6-GPIO45)") (class "Default")
      (node (ref "R30") (pin "1") (pinfunction "1_1") (pintype "passive"))
      (node (ref "U6") (pin "26") (pinfunction "GPIO45_26") (pintype "passive"))
    )
    (net (code "74") (name "Net-(U6-GPIO46)") (class "Default")
      (node (ref "R31") (pin "1") (pinfunction "1_1") (pintype "passive"))
      (node (ref "U6") (pin "16") (pinfunction "GPIO46_16") (pintype "passive"))
    )
    (net (code "75") (name "VBUS_A") (class "Default")
      (node (ref "C1") (pin "2") (pinfunction "2_2") (pintype "passive"))
      (node (ref "D1") (pin "K") (pinfunction "P$2_K") (pintype "passive"))
      (node (ref "J2") (pin "A4_B9") (pinfunction "VBUS_A4_B9") (pintype "power_in"))
      (node (ref "J2") (pin "B4_A9") (pinfunction "VBUS_B4_A9") (pintype "power_in"))
      (node (ref "R5") (pin "2") (pinfunction "2_2") (pintype "passive"))
      (node (ref "U3") (pin "1") (pinfunction "VBUS1_1") (pintype "power_in"))
    )
    (net (code "76") (name "VBUS_B") (class "Default")
      (node (ref "C2") (pin "2") (pinfunction "2_2") (pintype "passive"))
      (node (ref "D2") (pin "K") (pinfunction "P$2_K") (pintype "passive"))
      (node (ref "J3") (pin "A4_B9") (pinfunction "VBUS_A4_B9") (pintype "power_in"))
      (node (ref "J3") (pin "B4_A9") (pinfunction "VBUS_B4_A9") (pintype "power_in"))
      (node (ref "U4") (pin "1") (pinfunction "VBUS1_1") (pintype "power_in"))
    )
    (net (code "77") (name "unconnected-(D7-DO-Pad2-DOUT)") (class "Default")
      (node (ref "D7") (pin "2-DOUT") (pinfunction "DO_2-DOUT") (pintype "output+no_connect"))
    )
    (net (code "78") (name "unconnected-(J2-SBU1-PadA8)") (class "Default")
      (node (ref "J2") (pin "A8") (pinfunction "SBU1_A8") (pintype "bidirectional+no_connect"))
    )
    (net (code "79") (name "unconnected-(J2-SBU2-PadB8)") (class "Default")
      (node (ref "J2") (pin "B8") (pinfunction "SBU2_B8") (pintype "bidirectional+no_connect"))
    )
    (net (code "80") (name "unconnected-(J3-SBU1-PadA8)") (class "Default")
      (node (ref "J3") (pin "A8") (pinfunction "SBU1_A8") (pintype "bidirectional+no_connect"))
    )
    (net (code "81") (name "unconnected-(J3-SBU2-PadB8)") (class "Default")
      (node (ref "J3") (pin "B8") (pinfunction "SBU2_B8") (pintype "bidirectional+no_connect"))
    )
    (net (code "82") (name "unconnected-(U5-CHR0-Pad15)") (class "Default")
      (node (ref "U5") (pin "15") (pinfunction "CHR0_15") (pintype "output+no_connect"))
    )
    (net (code "83") (name "unconnected-(U5-CHR1-Pad14)") (class "Default")
      (node (ref "U5") (pin "14") (pinfunction "CHR1_14") (pintype "output+no_connect"))
    )
    (net (code "84") (name "unconnected-(U5-CHREN-Pad13)") (class "Default")
      (node (ref "U5") (pin "13") (pinfunction "CHREN_13") (pintype "output+no_connect"))
    )
    (net (code "85") (name "unconnected-(U5-CTS-Pad23)") (class "Default")
      (node (ref "U5") (pin "23") (pinfunction "CTS_23") (pintype "input+no_connect"))
    )
    (net (code "86") (name "unconnected-(U5-DCD-Pad1)") (class "Default")
      (node (ref "U5") (pin "1") (pinfunction "DCD_1") (pintype "input+no_connect"))
    )
    (net (code "87") (name "unconnected-(U5-DSR-Pad27)") (class "Default")
      (node (ref "U5") (pin "27") (pinfunction "DSR_27") (pintype "input+no_connect"))
    )
    (net (code "88") (name "unconnected-(U5-GPIO0_TXT-Pad19)") (class "Default")
      (node (ref "U5") (pin "19") (pinfunction "GPIO0_TXT_19") (pintype "bidirectional+no_connect"))
    )
    (net (code "89") (name "unconnected-(U5-GPIO1_RXT-Pad18)") (class "Default")
      (node (ref "U5") (pin "18") (pinfunction "GPIO1_RXT_18") (pintype "bidirectional+no_connect"))
    )
    (net (code "90") (name "unconnected-(U5-GPIO2_RS485-Pad17)") (class "Default")
      (node (ref "U5") (pin "17") (pinfunction "GPIO2_RS485_17") (pintype "bidirectional+no_connect"))
    )
    (net (code "91") (name "unconnected-(U5-GPIO3_WAKEUP-Pad16)") (class "Default")
      (node (ref "U5") (pin "16") (pinfunction "GPIO3_WAKEUP_16") (pintype "bidirectional+no_connect"))
    )
    (net (code "92") (name "unconnected-(U5-GPIO4-Pad22)") (class "Default")
      (node (ref "U5") (pin "22") (pinfunction "GPIO4_22") (pintype "bidirectional+no_connect"))
    )
    (net (code "93") (name "unconnected-(U5-GPIO5-Pad21)") (class "Default")
      (node (ref "U5") (pin "21") (pinfunction "GPIO5_21") (pintype "bidirectional+no_connect"))
    )
    (net (code "94") (name "unconnected-(U5-GPIO6-Pad20)") (class "Default")
      (node (ref "U5") (pin "20") (pinfunction "GPIO6_20") (pintype "bidirectional+no_connect"))
    )
    (net (code "95") (name "unconnected-(U5-NC-Pad10)") (class "Default")
      (node (ref "U5") (pin "10") (pinfunction "NC_10") (pintype "passive+no_connect"))
    )
    (net (code "96") (name "unconnected-(U5-RI{slash}CLK-Pad2)") (class "Default")
      (node (ref "U5") (pin "2") (pinfunction "RI/CLK_2") (pintype "bidirectional+no_connect"))
    )
    (net (code "97") (name "unconnected-(U5-SUSPEND-Pad12)") (class "Default")
      (node (ref "U5") (pin "12") (pinfunction "SUSPEND_12") (pintype "output+no_connect"))
    )
    (net (code "98") (name "unconnected-(U6-GPIO3-Pad15)") (class "Default")
      (node (ref "U6") (pin "15") (pinfunction "GPIO3_15") (pintype "passive+no_connect"))
    )
    (net (code "99") (name "unconnected-(U6-GPIO16_{slash}_U0CTS_{slash}_XTAL_32K_N-Pad9)") (class "Default")
      (node (ref "U6") (pin "9") (pinfunction "GPIO16_/_U0CTS_/_XTAL_32K_N_9") (pintype "passive+no_connect"))
    )
    (net (code "100") (name "unconnected-(U6-GPIO21-Pad23)") (class "Default")
      (node (ref "U6") (pin "23") (pinfunction "GPIO21_23") (pintype "passive+no_connect"))
    )
    (net (code "101") (name "unconnected-(U6-GPIO39_{slash}_MTCK-Pad32)") (class "Default")
      (node (ref "U6") (pin "32") (pinfunction "GPIO39_/_MTCK_32") (pintype "passive+no_connect"))
    )
    (net (code "102") (name "unconnected-(U6-GPIO40_{slash}_MTDO-Pad33)") (class "Default")
      (node (ref "U6") (pin "33") (pinfunction "GPIO40_/_MTDO_33") (pintype "passive+no_connect"))
    )
    (net (code "103") (name "unconnected-(U6-GPIO41_{slash}_MTDI-Pad34)") (class "Default")
      (node (ref "U6") (pin "34") (pinfunction "GPIO41_/_MTDI_34") (pintype "passive+no_connect"))
    )
    (net (code "104") (name "unconnected-(U6-GPIO42_{slash}_MTMS-Pad35)") (class "Default")
      (node (ref "U6") (pin "35") (pinfunction "GPIO42_/_MTMS_35") (pintype "passive+no_connect"))
    )
    (net (code "105") (name "unconnected-(U6-GPIO47-Pad24)") (class "Default")
      (node (ref "U6") (pin "24") (pinfunction "GPIO47_24") (pintype "passive+no_connect"))
    )
    (net (code "106") (name "unconnected-(U6-GPIO48-Pad25)") (class "Default")
      (node (ref "U6") (pin "25") (pinfunction "GPIO48_25") (pintype "passive+no_connect"))
    )
    (net (code "107") (name "unconnected-(U6-NC-Pad28)") (class "Default")
      (node (ref "U6") (pin "28") (pinfunction "NC_28") (pintype "passive+no_connect"))
    )
    (net (code "108") (name "unconnected-(U6-NC-Pad29)") (class "Default")
      (node (ref "U6") (pin "29") (pinfunction "NC_29") (pintype "passive+no_connect"))
    )
    (net (code "109") (name "unconnected-(U6-NC-Pad30)") (class "Default")
      (node (ref "U6") (pin "30") (pinfunction "NC_30") (pintype "passive+no_connect"))
    )
  )
)
